# STEP_MOTOR_ISOLATOR_INPUT.net
KiCad netlist of a schematic drawn in Altium Designer
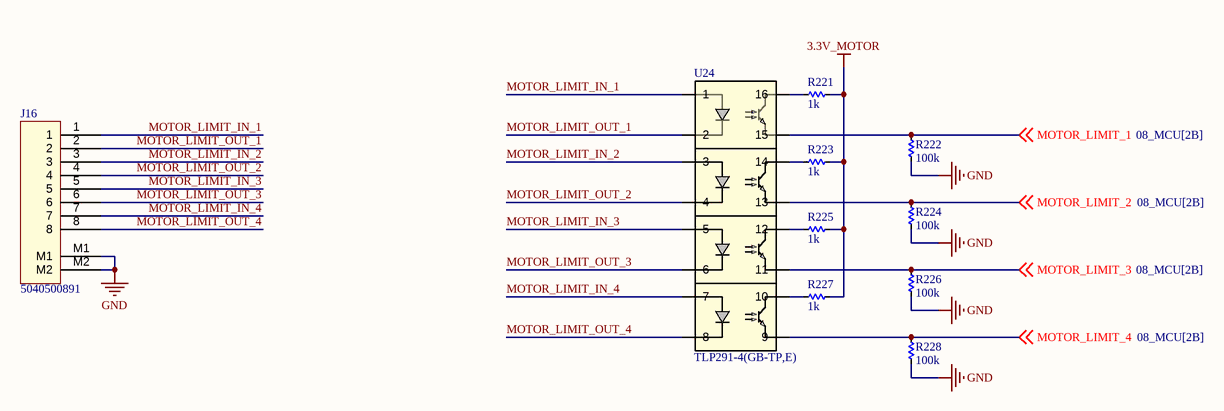
[diagram p0: STEP_MOTOR_ISOLATOR_INPUT.SchDoc]

(export (version "E")
  (design (tool "Eeschema 10.0.6"))
  (components
    (comp (ref "J16")
      (value "5040500891")
      (footprint "MOLEX_5040500891")
      (libsource (lib "LABLIB") (part "Header 8x1_2M"))
    )
    (comp (ref "R221")
      (value "1k")
      (footprint "RES_C_1005X40")
      (description "RES")
      (libsource (lib "LABLIB") (part "_RES_B_2"))
    )
    (comp (ref "R222")
      (value "100k")
      (footprint "RES_C_1005X40")
      (description "RES")
      (libsource (lib "LABLIB") (part "_RES_B_2"))
    )
    (comp (ref "R223")
      (value "1k")
      (footprint "RES_C_1005X40")
      (description "RES")
      (libsource (lib "LABLIB") (part "_RES_B_2"))
    )
    (comp (ref "R224")
      (value "100k")
      (footprint "RES_C_1005X40")
      (description "RES")
      (libsource (lib "LABLIB") (part "_RES_B_2"))
    )
    (comp (ref "R225")
      (value "1k")
      (footprint "RES_C_1005X40")
      (description "RES")
      (libsource (lib "LABLIB") (part "_RES_B_2"))
    )
    (comp (ref "R226")
      (value "100k")
      (footprint "RES_C_1005X40")
      (description "RES")
      (libsource (lib "LABLIB") (part "_RES_B_2"))
    )
    (comp (ref "R227")
      (value "1k")
      (footprint "RES_C_1005X40")
      (description "RES")
      (libsource (lib "LABLIB") (part "_RES_B_2"))
    )
    (comp (ref "R228")
      (value "100k")
      (footprint "RES_C_1005X40")
      (description "RES")
      (libsource (lib "LABLIB") (part "_RES_B_2"))
    )
    (comp (ref "U24")
      (value "TLP291-4(GB-TP,E)")
      (footprint "SO16_TOS")
      (description "Description")
      (fields (field (name "COPYRIGHT") "Copyright (C) 2026 Ultra Librarian. All rights reserved."))
      (libsource (lib "BEE-DAL_EXP_sche") (part "TLP291-4GB-TP,E"))
    )
  )
  (nets
    (net (code "1") (name "/MOTOR_LIMIT_IN_1") (class "Default")
      (node (ref "J16") (pin "1") (pinfunction "1_1") (pintype "passive"))
      (node (ref "U24") (pin "1") (pinfunction "1_1") (pintype "passive"))
    )
    (net (code "2") (name "/MOTOR_LIMIT_IN_2") (class "Default")
      (node (ref "J16") (pin "3") (pinfunction "3_3") (pintype "passive"))
      (node (ref "U24") (pin "3") (pinfunction "3_3") (pintype "passive"))
    )
    (net (code "3") (name "/MOTOR_LIMIT_IN_3") (class "Default")
      (node (ref "J16") (pin "5") (pinfunction "5_5") (pintype "passive"))
      (node (ref "U24") (pin "5") (pinfunction "5_5") (pintype "passive"))
    )
    (net (code "4") (name "/MOTOR_LIMIT_IN_4") (class "Default")
      (node (ref "J16") (pin "7") (pinfunction "7_7") (pintype "passive"))
      (node (ref "U24") (pin "7") (pinfunction "7_7") (pintype "passive"))
    )
    (net (code "5") (name "/MOTOR_LIMIT_OUT_1") (class "Default")
      (node (ref "J16") (pin "2") (pinfunction "2_2") (pintype "passive"))
      (node (ref "U24") (pin "2") (pinfunction "2_2") (pintype "passive"))
    )
    (net (code "6") (name "/MOTOR_LIMIT_OUT_2") (class "Default")
      (node (ref "J16") (pin "4") (pinfunction "4_4") (pintype "passive"))
      (node (ref "U24") (pin "4") (pinfunction "4_4") (pintype "passive"))
    )
    (net (code "7") (name "/MOTOR_LIMIT_OUT_3") (class "Default")
      (node (ref "J16") (pin "6") (pinfunction "6_6") (pintype "passive"))
      (node (ref "U24") (pin "6") (pinfunction "6_6") (pintype "passive"))
    )
    (net (code "8") (name "/MOTOR_LIMIT_OUT_4") (class "Default")
      (node (ref "J16") (pin "8") (pinfunction "8_8") (pintype "passive"))
      (node (ref "U24") (pin "8") (pinfunction "8_8") (pintype "passive"))
    )
    (net (code "9") (name "3.3V_MOTOR") (class "Default")
      (node (ref "R221") (pin "1") (pinfunction "1_1") (pintype "passive"))
      (node (ref "R223") (pin "1") (pinfunction "1_1") (pintype "passive"))
      (node (ref "R225") (pin "1") (pinfunction "1_1") (pintype "passive"))
      (node (ref "R227") (pin "1") (pinfunction "1_1") (pintype "passive"))
    )
    (net (code "10") (name "GND") (class "Default")
      (node (ref "J16") (pin "M1") (pinfunction "M1_M1") (pintype "passive"))
      (node (ref "J16") (pin "M2") (pinfunction "M2_M2") (pintype "passive"))
      (node (ref "R222") (pin "1") (pinfunction "1_1") (pintype "passive"))
      (node (ref "R224") (pin "1") (pinfunction "1_1") (pintype "passive"))
      (node (ref "R226") (pin "1") (pinfunction "1_1") (pintype "passive"))
      (node (ref "R228") (pin "1") (pinfunction "1_1") (pintype "passive"))
    )
    (net (code "11") (name "MOTOR_LIMIT_1") (class "Default")
      (node (ref "R222") (pin "2") (pinfunction "2_2") (pintype "passive"))
      (node (ref "U24") (pin "15") (pinfunction "15_15") (pintype "passive"))
    )
    (net (code "12") (name "MOTOR_LIMIT_2") (class "Default")
      (node (ref "R224") (pin "2") (pinfunction "2_2") (pintype "passive"))
      (node (ref "U24") (pin "13") (pinfunction "13_13") (pintype "passive"))
    )
    (net (code "13") (name "MOTOR_LIMIT_3") (class "Default")
      (node (ref "R226") (pin "2") (pinfunction "2_2") (pintype "passive"))
      (node (ref "U24") (pin "11") (pinfunction "11_11") (pintype "passive"))
    )
    (net (code "14") (name "MOTOR_LIMIT_4") (class "Default")
      (node (ref "R228") (pin "2") (pinfunction "2_2") (pintype "passive"))
      (node (ref "U24") (pin "9") (pinfunction "9_9") (pintype "passive"))
    )
    (net (code "15") (name "Net-(R221-Pad2)") (class "Default")
      (node (ref "R221") (pin "2") (pinfunction "2_2") (pintype "passive"))
      (node (ref "U24") (pin "16") (pinfunction "16_16") (pintype "passive"))
    )
    (net (code "16") (name "Net-(R223-Pad2)") (class "Default")
      (node (ref "R223") (pin "2") (pinfunction "2_2") (pintype "passive"))
      (node (ref "U24") (pin "14") (pinfunction "14_14") (pintype "passive"))
    )
    (net (code "17") (name "Net-(R225-Pad2)") (class "Default")
      (node (ref "R225") (pin "2") (pinfunction "2_2") (pintype "passive"))
      (node (ref "U24") (pin "12") (pinfunction "12_12") (pintype "passive"))
    )
    (net (code "18") (name "Net-(R227-Pad2)") (class "Default")
      (node (ref "R227") (pin "2") (pinfunction "2_2") (pintype "passive"))
      (node (ref "U24") (pin "10") (pinfunction "10_10") (pintype "passive"))
    )
  )
)
